# Sheet1.net
KiCad netlist of a schematic drawn in Altium Designer
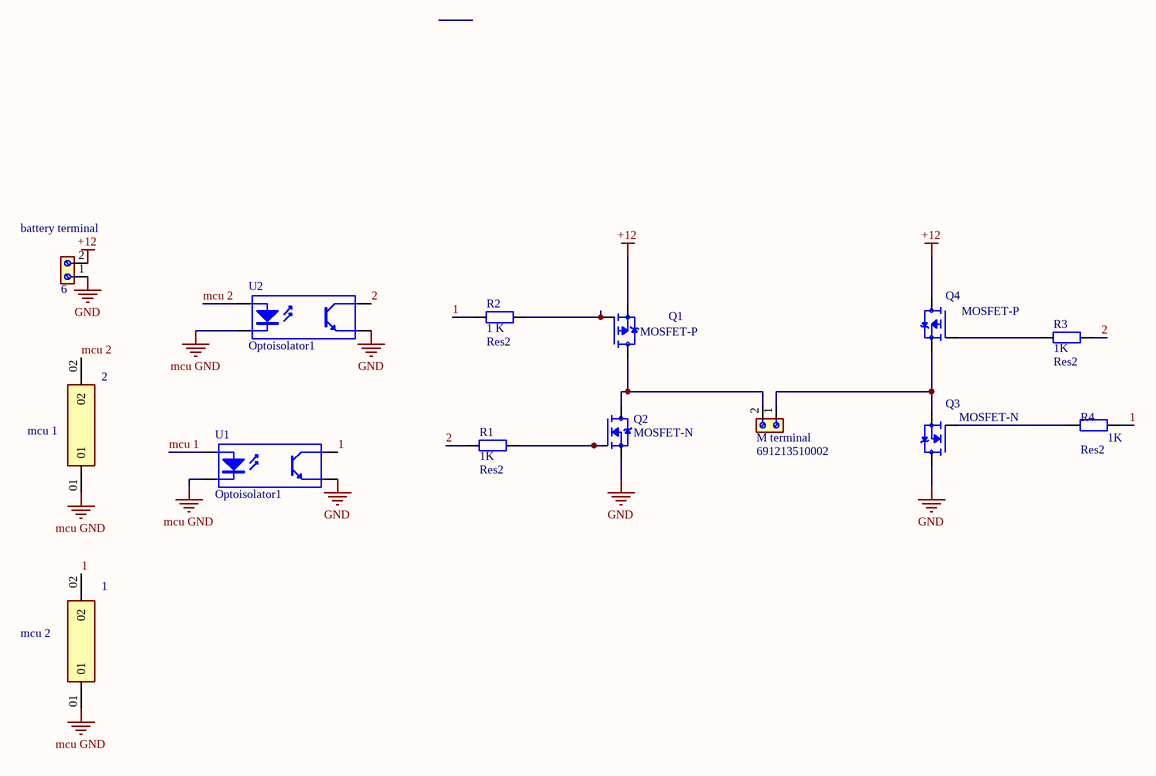
[diagram p0: Sheet1.SchDoc]

(export (version "E")
  (design (tool "Eeschema 10.0.6"))
  (components
    (comp (ref "1")
      (value "mcu 2")
      (footprint "SAMTEC_MTMM-101-15-G-D-105")
      (description "Connector Header Through Hole 2 position")
      (fields (field (name "MP") "MTMM-101-15-G-D-105") (field (name "MF") "Samtec"))
      (libsource (lib "MTMM-101-15-G-D-105") (part "MTMM-101-15-G-D-105"))
    )
    (comp (ref "2")
      (value "mcu 1")
      (footprint "SAMTEC_MTMM-101-15-G-D-105")
      (description "Connector Header Through Hole 2 position")
      (fields (field (name "MP") "MTMM-101-15-G-D-105") (field (name "MF") "Samtec"))
      (libsource (lib "MTMM-101-15-G-D-105") (part "MTMM-101-15-G-D-105"))
    )
    (comp (ref "battery terminal")
      (value "6")
      (footprint "691213510002")
      (description "2 Position Wire to Board Terminal Block Horizontal with Board 0.200 (5.08mm) Through Hole")
      (fields (field (name "MF") "Wurth Electronics") (field (name "MP") "691213510002"))
      (libsource (lib "termina") (part "691213510002"))
    )
    (comp (ref "M terminal")
      (value "691213510002")
      (footprint "691213510002")
      (description "2 Position Wire to Board Terminal Block Horizontal with Board 0.200 (5.08mm) Through Hole")
      (fields (field (name "MF") "Wurth Electronics"))
      (libsource (lib "") (part "691213510002_1"))
    )
    (comp (ref "Q1")
      (value "MOSFET-P")
      (footprint "TO545P2000X491X2918-3")
      (description "P CHANNEL LATERAL MOSFET")
      (fields (field (name "MP") "ECW20P20"))
      (libsource (lib "p mosfet.") (part "ECW20P20"))
    )
    (comp (ref "Q2")
      (value "MOSFET-N")
      (footprint "TO254P1036X470X1965-3")
      (description "80-V, N channel NexFETâ„¢ power MOSFET, single TO-220, 9.2 mOhm")
      (fields (field (name "MP") "CSD19503KCS") (field (name "MF") "Texas Instruments"))
      (libsource (lib "nnnnn") (part "CSD19503KCS"))
    )
    (comp (ref "Q3")
      (value "MOSFET-N")
      (footprint "TO254P1036X470X1965-3")
      (description "80-V, N channel NexFETâ„¢ power MOSFET, single TO-220, 9.2 mOhm")
      (fields (field (name "MP") "CSD19503KCS") (field (name "MF") "Texas Instruments"))
      (libsource (lib "nnnnn") (part "CSD19503KCS"))
    )
    (comp (ref "Q4")
      (value "MOSFET-P")
      (footprint "TO545P2000X491X2918-3")
      (description "P CHANNEL LATERAL MOSFET")
      (fields (field (name "MP") "ECW20P20"))
      (libsource (lib "p mosfet.") (part "ECW20P20"))
    )
    (comp (ref "R1")
      (value "Res2")
      (footprint "AXIAL-0.4")
      (description "Resistor")
      (fields (field (name "ALTIUM_VALUE") "1K") (field (name "PUBLISHER") "Altium Limited"))
      (libsource (lib "Miscellaneous Devices") (part "Res2"))
    )
    (comp (ref "R2")
      (value "Res2")
      (footprint "AXIAL-0.4")
      (description "Resistor")
      (fields (field (name "ALTIUM_VALUE") "1 K") (field (name "PUBLISHER") "Altium Limited"))
      (libsource (lib "") (part "Res2_1"))
    )
    (comp (ref "R3")
      (value "Res2")
      (footprint "AXIAL-0.4")
      (description "Resistor")
      (fields (field (name "ALTIUM_VALUE") "1K") (field (name "PUBLISHER") "Altium Limited"))
      (libsource (lib "Miscellaneous Devices") (part "Res2"))
    )
    (comp (ref "R4")
      (value "Res2")
      (footprint "AXIAL-0.4")
      (description "Resistor")
      (fields (field (name "ALTIUM_VALUE") "1K") (field (name "PUBLISHER") "Altium Limited"))
      (libsource (lib "Miscellaneous Devices") (part "Res2"))
    )
    (comp (ref "U1")
      (value "Optoisolator1")
      (footprint "DIP-4")
      (description "4-Pin Phototransistor Optocoupler")
      (fields (field (name "PUBLISHER") "Altium Limited"))
      (libsource (lib "Miscellaneous Devices") (part "Optoisolator1"))
    )
    (comp (ref "U2")
      (value "Optoisolator1")
      (footprint "DIP-4")
      (description "4-Pin Phototransistor Optocoupler")
      (fields (field (name "PUBLISHER") "Altium Limited"))
      (libsource (lib "Miscellaneous Devices") (part "Optoisolator1"))
    )
  )
  (nets
    (net (code "1") (name "+12") (class "Default")
      (node (ref "Q1") (pin "2") (pinfunction "S_2") (pintype "passive"))
      (node (ref "Q4") (pin "3") (pinfunction "D_3") (pintype "passive"))
      (node (ref "battery terminal") (pin "2") (pinfunction "2_2") (pintype "passive"))
    )
    (net (code "2") (name "/1") (class "Default")
      (node (ref "1") (pin "02") (pinfunction "02_02") (pintype "passive"))
      (node (ref "R2") (pin "2") (pinfunction "2_2") (pintype "passive"))
      (node (ref "R4") (pin "2") (pinfunction "2_2") (pintype "passive"))
      (node (ref "U1") (pin "4") (pinfunction "C_4") (pintype "passive"))
    )
    (net (code "3") (name "/2") (class "Default")
      (node (ref "R1") (pin "1") (pinfunction "1_1") (pintype "passive"))
      (node (ref "R3") (pin "2") (pinfunction "2_2") (pintype "passive"))
      (node (ref "U2") (pin "4") (pinfunction "C_4") (pintype "passive"))
    )
    (net (code "4") (name "/mcu 1") (class "Default")
      (node (ref "U1") (pin "1") (pinfunction "A_1") (pintype "passive"))
    )
    (net (code "5") (name "/mcu 2") (class "Default")
      (node (ref "2") (pin "02") (pinfunction "02_02") (pintype "passive"))
      (node (ref "U2") (pin "1") (pinfunction "A_1") (pintype "passive"))
    )
    (net (code "6") (name "GND") (class "Default")
      (node (ref "Q2") (pin "3") (pinfunction "S_3") (pintype "passive"))
      (node (ref "Q3") (pin "2") (pinfunction "D_2") (pintype "passive"))
      (node (ref "U1") (pin "3") (pinfunction "E_3") (pintype "passive"))
      (node (ref "U2") (pin "3") (pinfunction "E_3") (pintype "passive"))
      (node (ref "battery terminal") (pin "1") (pinfunction "1_1") (pintype "passive"))
    )
    (net (code "7") (name "Net-(Q1-D)") (class "Default")
      (node (ref "M terminal") (pin "2") (pinfunction "2_2") (pintype "passive"))
      (node (ref "Q1") (pin "3") (pinfunction "D_3") (pintype "passive"))
      (node (ref "Q2") (pin "2") (pinfunction "D_2") (pintype "passive"))
    )
    (net (code "8") (name "Net-(Q1-G)") (class "Default")
      (node (ref "Q1") (pin "1") (pinfunction "G_1") (pintype "passive"))
      (node (ref "R2") (pin "1") (pinfunction "1_1") (pintype "passive"))
    )
    (net (code "9") (name "Net-(Q2-G)") (class "Default")
      (node (ref "Q2") (pin "1") (pinfunction "G_1") (pintype "passive"))
      (node (ref "R1") (pin "2") (pinfunction "2_2") (pintype "passive"))
    )
    (net (code "10") (name "Net-(Q3-G)") (class "Default")
      (node (ref "Q3") (pin "1") (pinfunction "G_1") (pintype "passive"))
      (node (ref "R4") (pin "1") (pinfunction "1_1") (pintype "passive"))
    )
    (net (code "11") (name "Net-(Q3-S)") (class "Default")
      (node (ref "M terminal") (pin "1") (pinfunction "1_1") (pintype "passive"))
      (node (ref "Q3") (pin "3") (pinfunction "S_3") (pintype "passive"))
      (node (ref "Q4") (pin "2") (pinfunction "S_2") (pintype "passive"))
    )
    (net (code "12") (name "Net-(Q4-G)") (class "Default")
      (node (ref "Q4") (pin "1") (pinfunction "G_1") (pintype "passive"))
      (node (ref "R3") (pin "1") (pinfunction "1_1") (pintype "passive"))
    )
    (net (code "13") (name "mcu GND") (class "Default")
      (node (ref "1") (pin "01") (pinfunction "01_01") (pintype "passive"))
      (node (ref "2") (pin "01") (pinfunction "01_01") (pintype "passive"))
      (node (ref "U1") (pin "2") (pinfunction "K_2") (pintype "passive"))
      (node (ref "U2") (pin "2") (pinfunction "K_2") (pintype "passive"))
    )
  )
)
